# BBB_CNC_V2.net
KiCad netlist of a schematic drawn in EAGLE
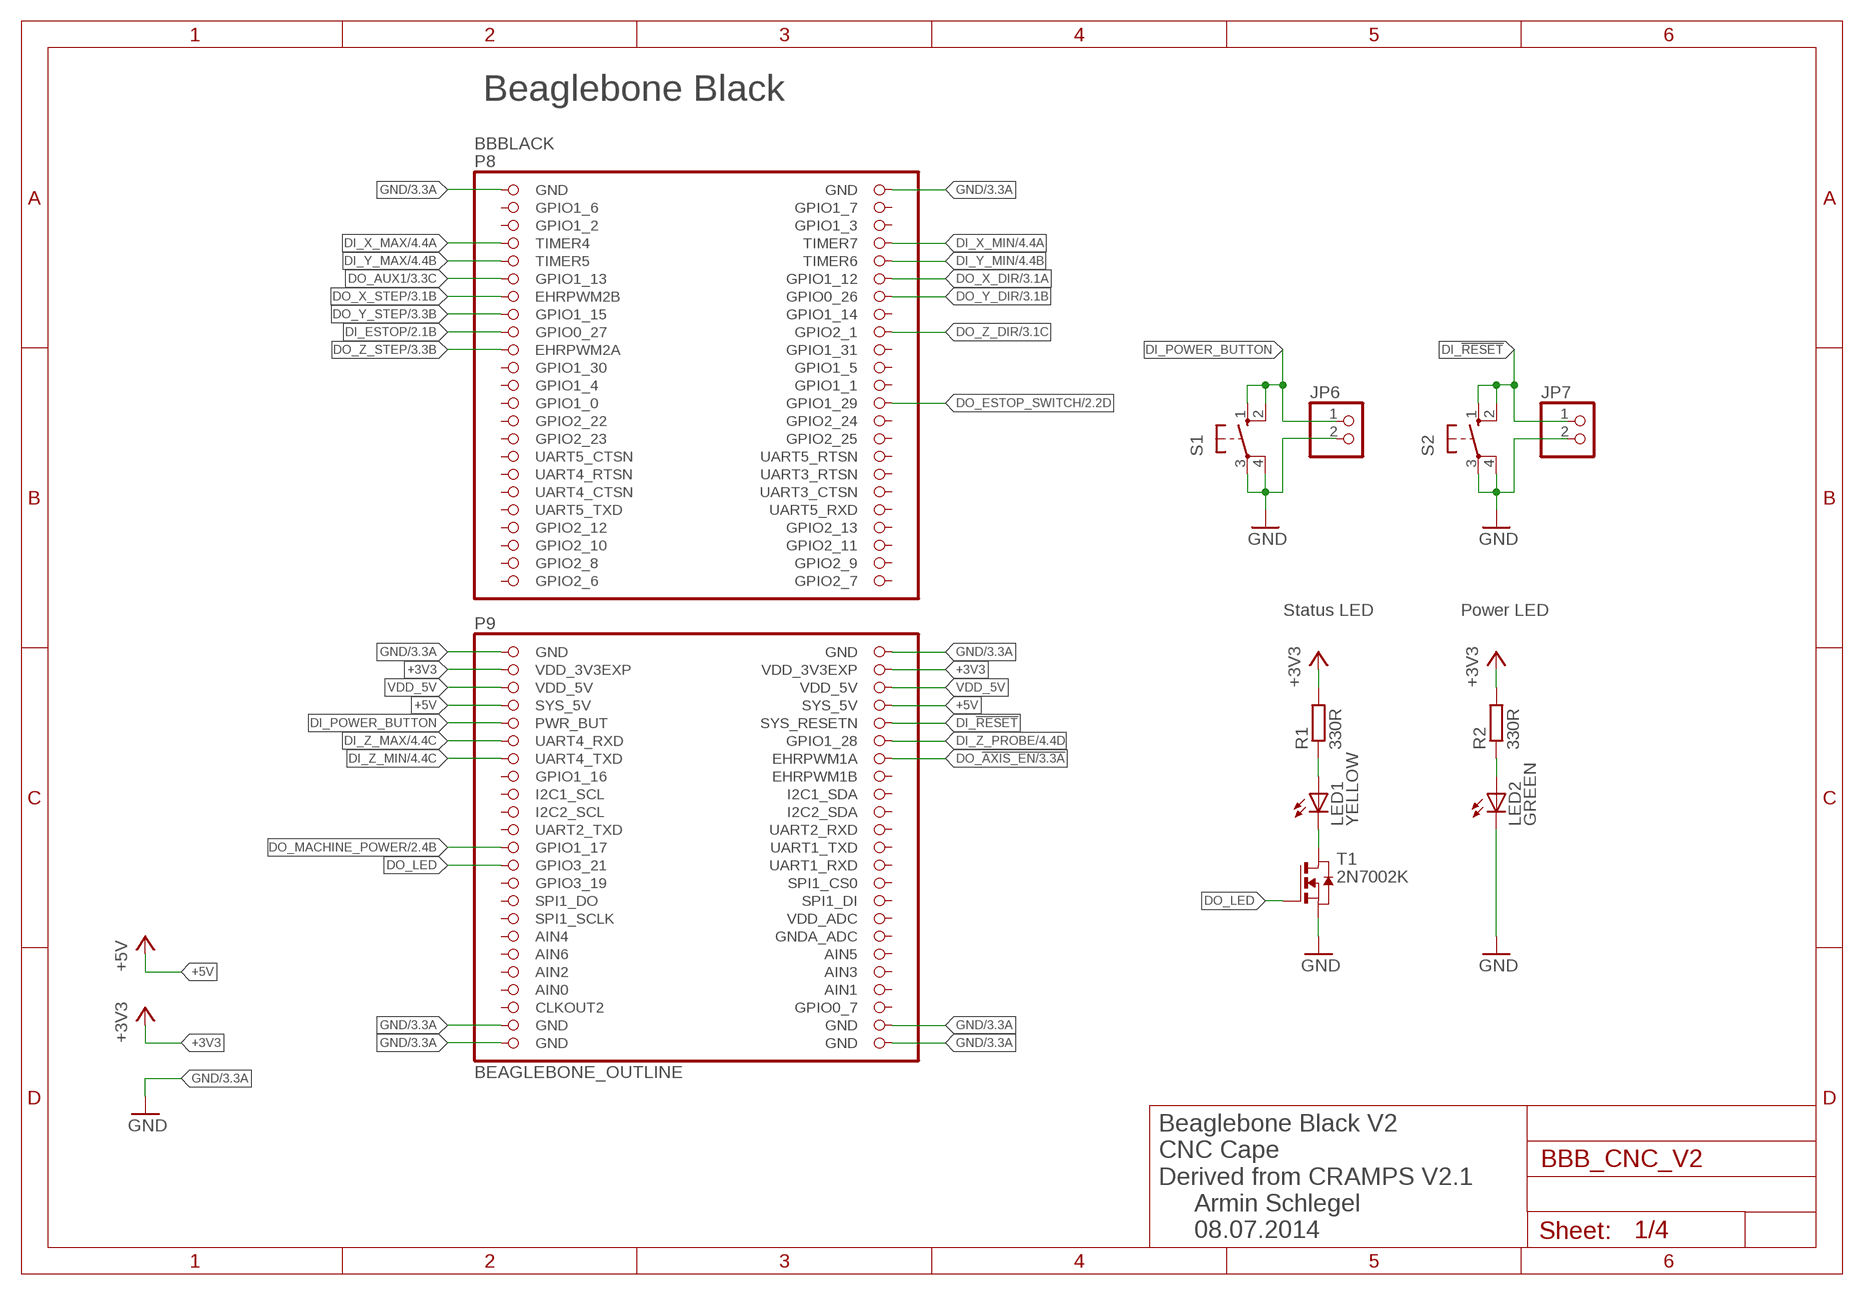
[diagram p0: schematic, sheet 1]
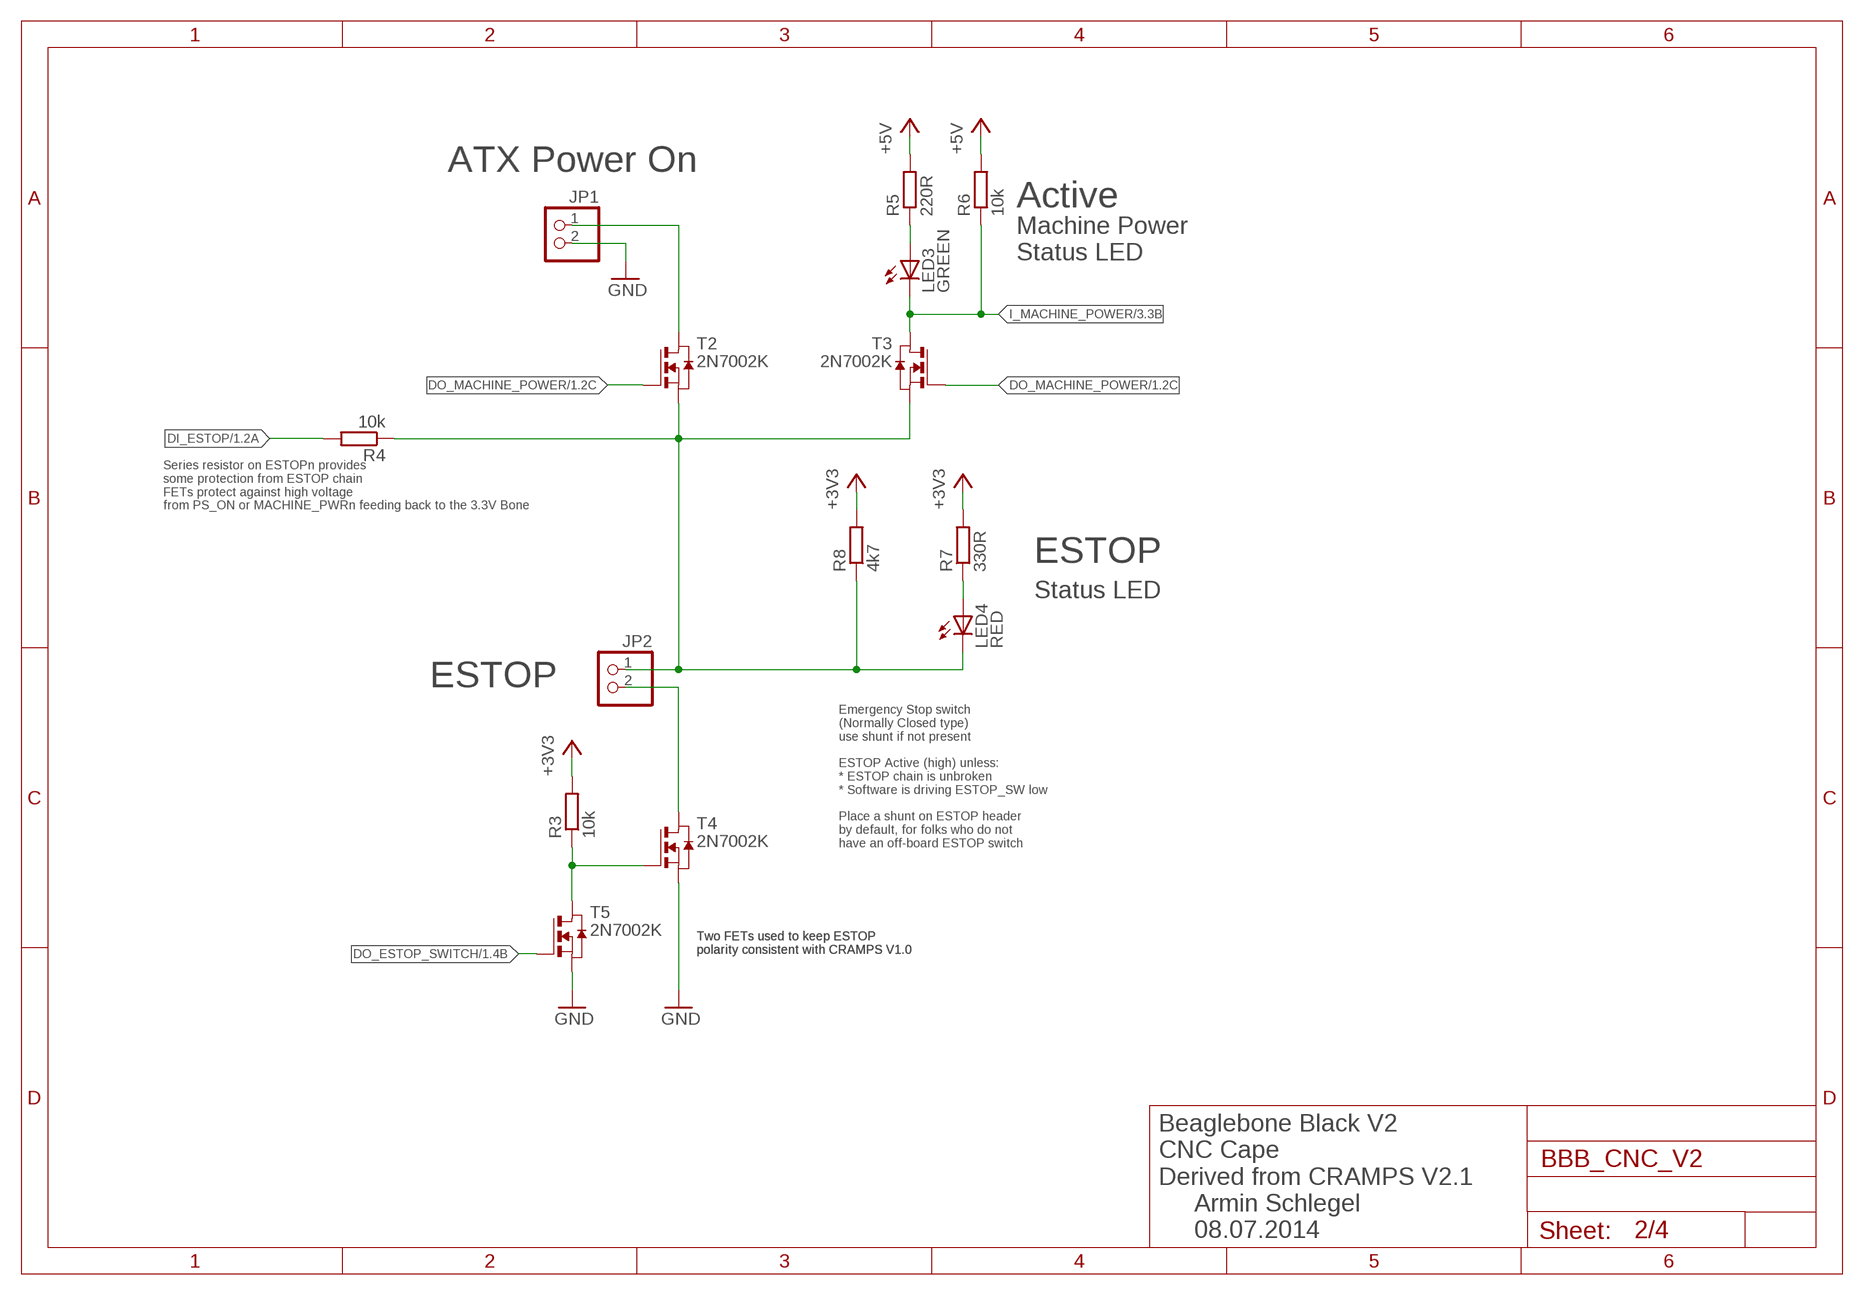
[diagram p1: schematic, sheet 2]
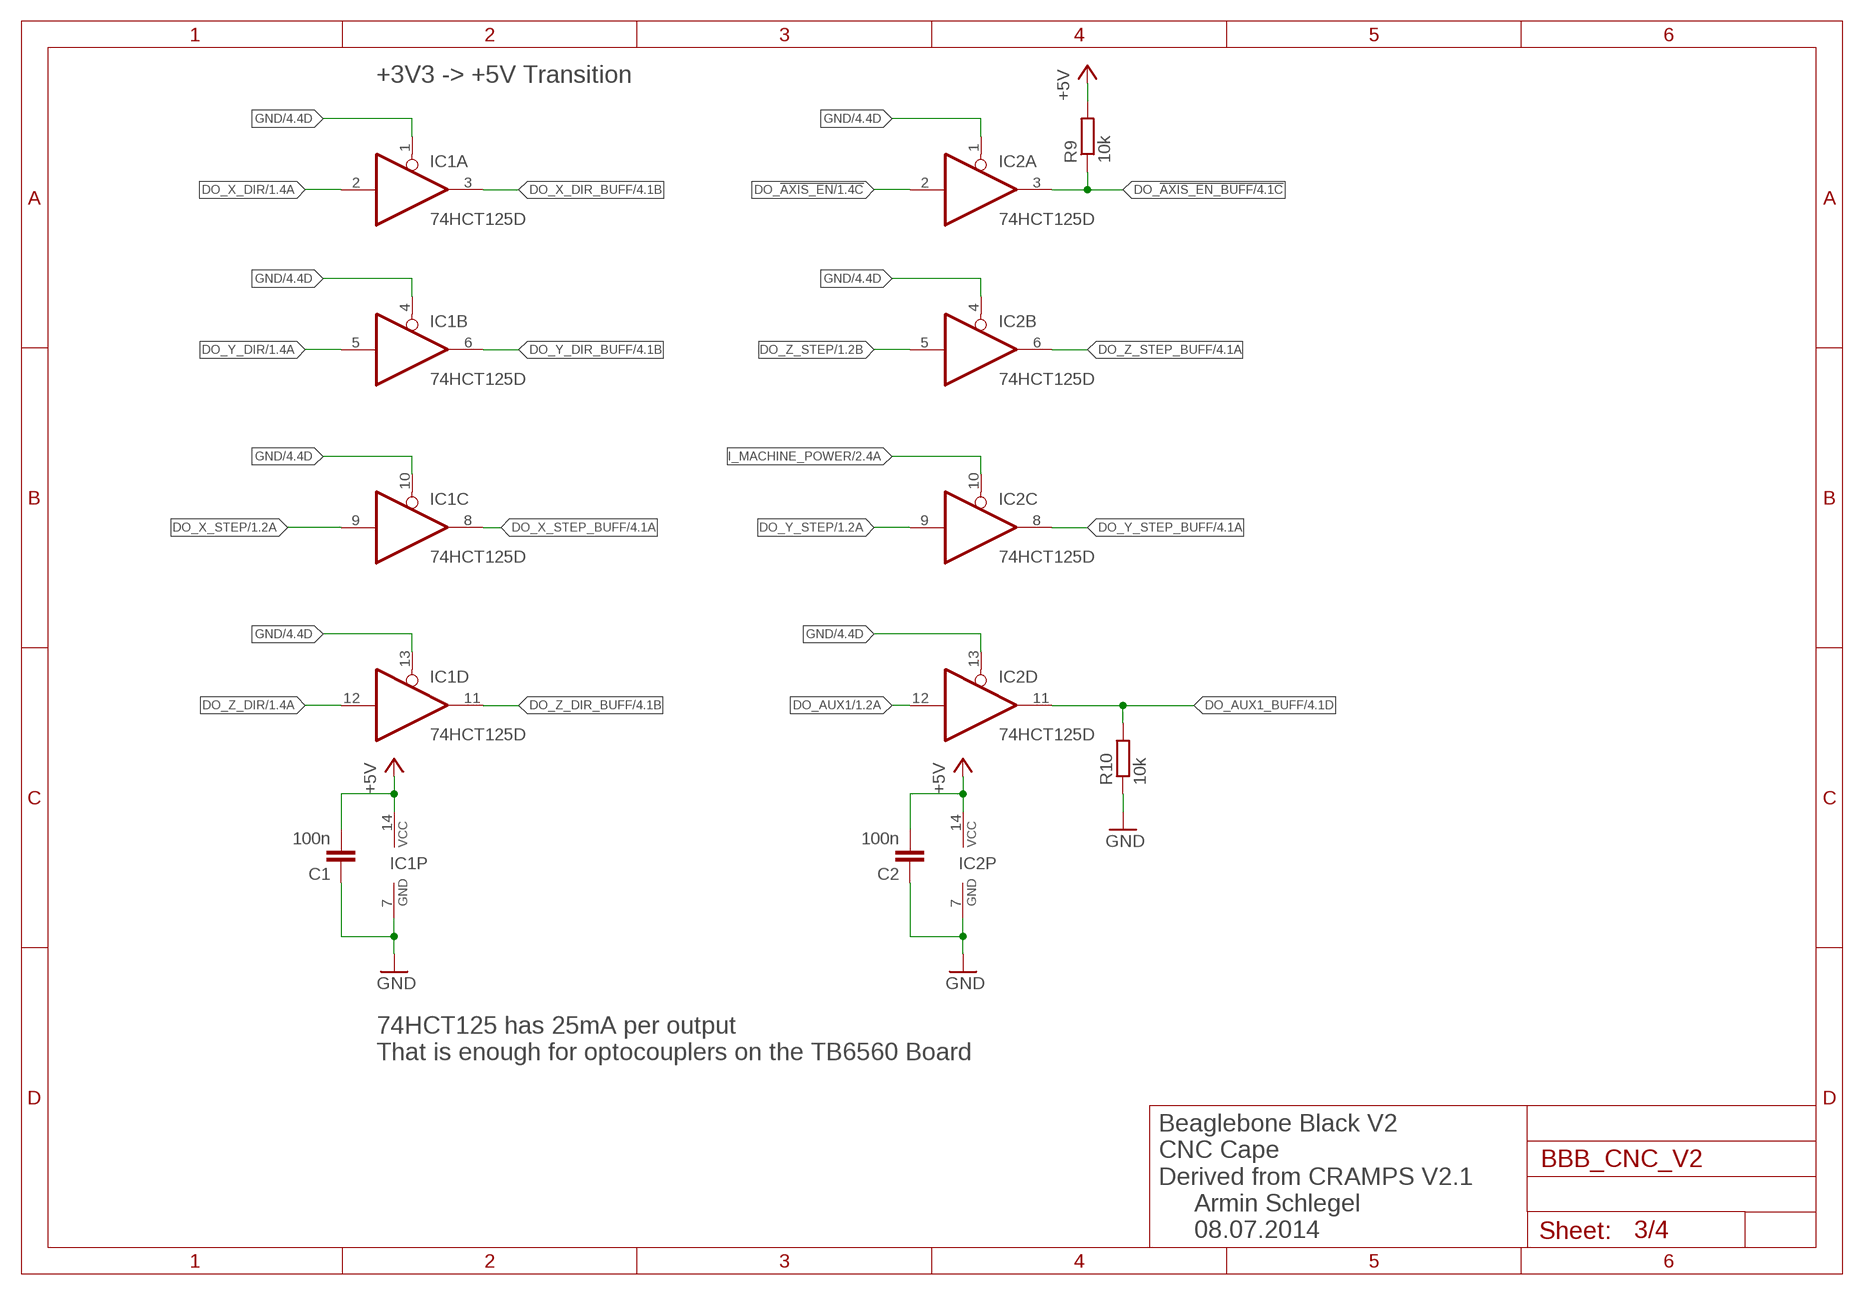
[diagram p2: schematic, sheet 3]
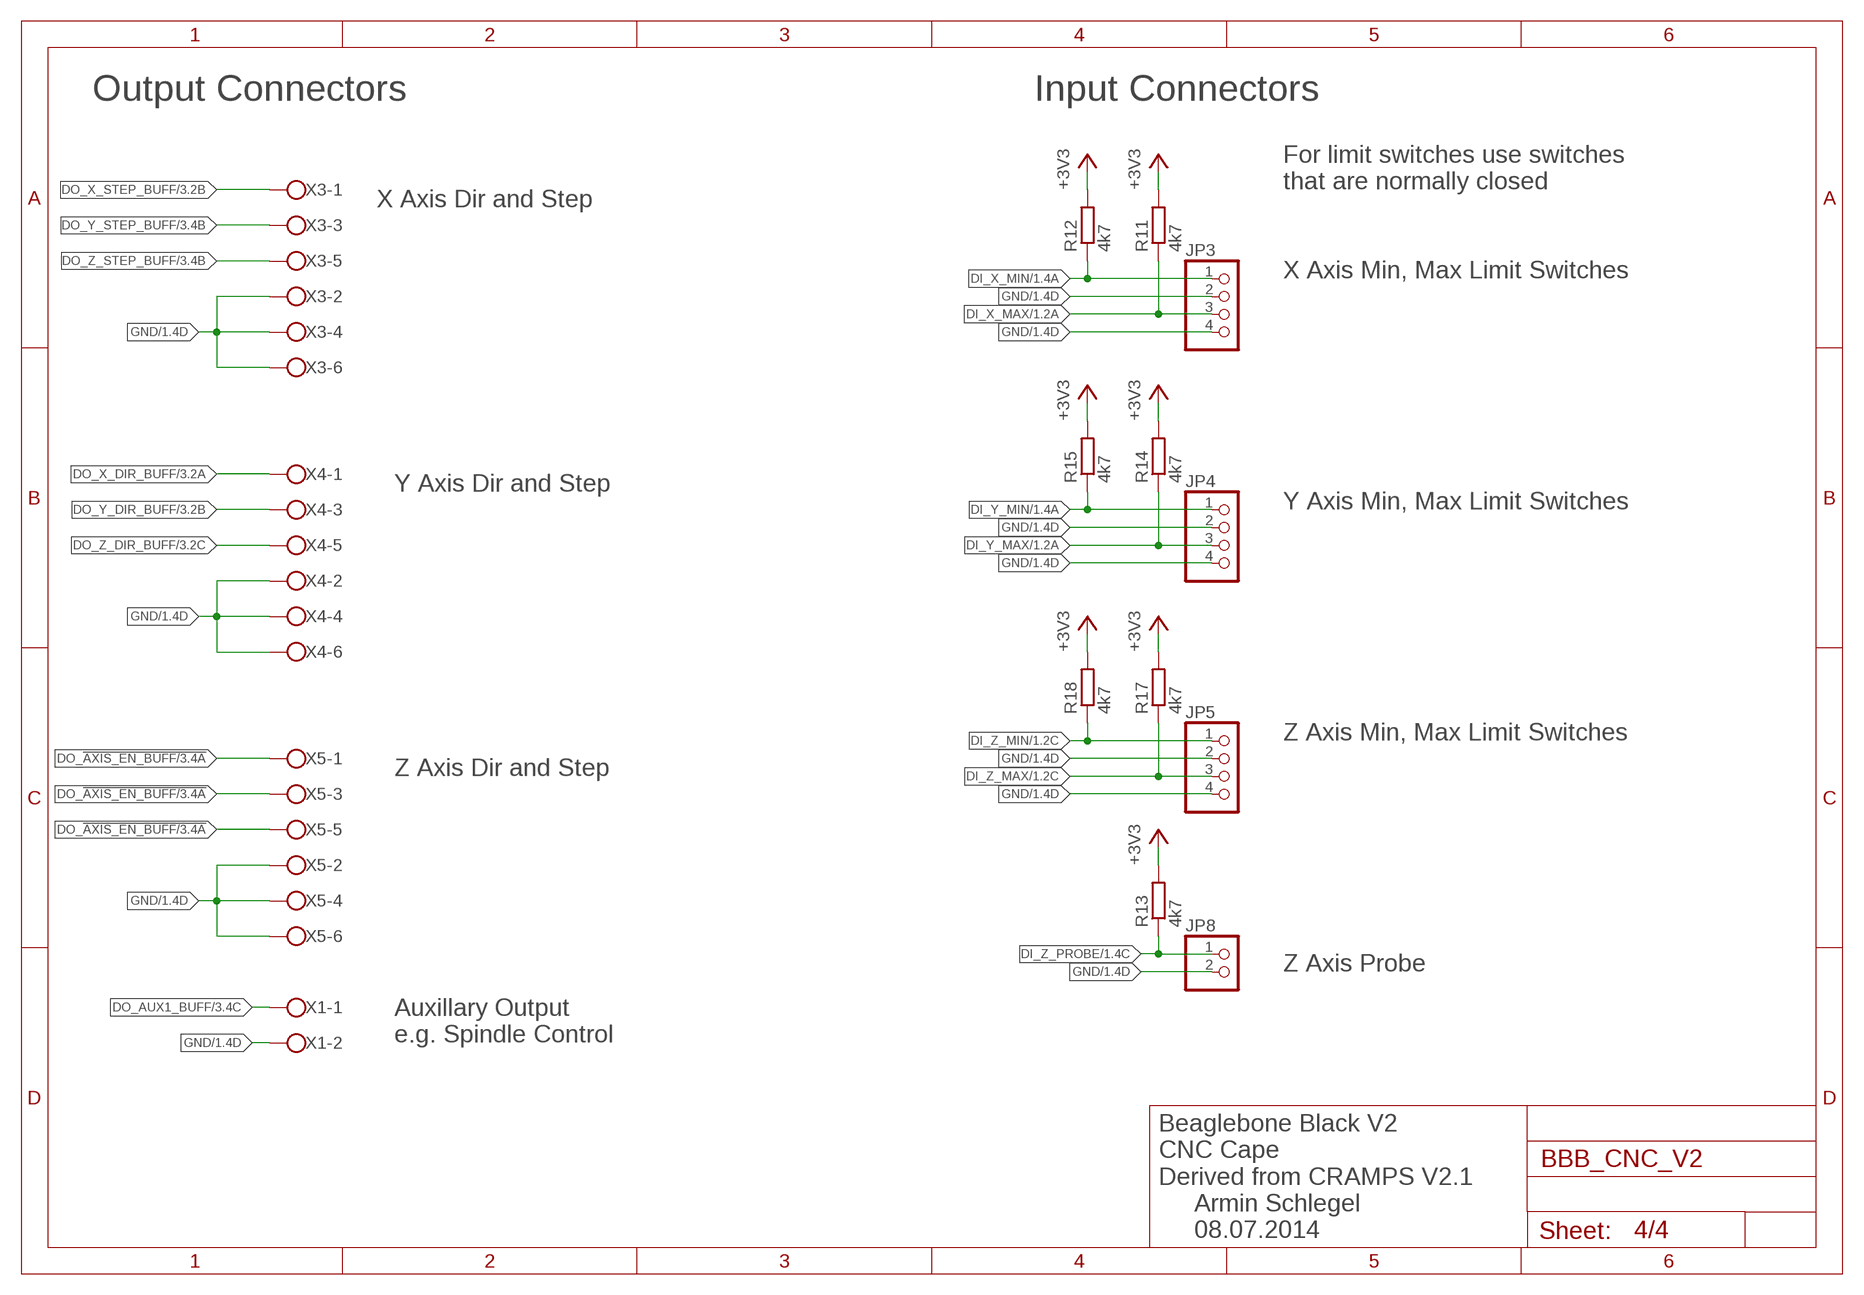
[diagram p3: schematic, sheet 4]

(export (version "E")
  (design (tool "Eeschema 10.0.6"))
  (components
    (comp (ref "BBBLACK")
      (value "BEAGLEBONE_OUTLINE")
      (footprint "eagle-import:BEAGLEBONE_SHIELD")
      (libsource (lib "eagle-import") (part "BEAGLEBONE_OUTLINE"))
    )
    (comp (ref "JP6")
      (value "PINHD-1X2")
      (footprint "eagle-import:1X02")
      (libsource (lib "eagle-import") (part "PINHD-1X2"))
    )
    (comp (ref "JP7")
      (value "PINHD-1X2")
      (footprint "eagle-import:1X02")
      (libsource (lib "eagle-import") (part "PINHD-1X2"))
    )
    (comp (ref "LED1")
      (value "YELLOW")
      (footprint "eagle-import:SML0805")
      (libsource (lib "eagle-import") (part "LEDSML0805"))
    )
    (comp (ref "LED2")
      (value "GREEN")
      (footprint "eagle-import:SML0805")
      (libsource (lib "eagle-import") (part "LEDSML0805"))
    )
    (comp (ref "R1")
      (value "330R")
      (footprint "eagle-import:R0603")
      (libsource (lib "eagle-import") (part "R-EU_R0603"))
    )
    (comp (ref "R2")
      (value "330R")
      (footprint "eagle-import:R0603")
      (libsource (lib "eagle-import") (part "R-EU_R0603"))
    )
    (comp (ref "S1")
      (value "10-XX")
      (footprint "eagle-import:B3F-10XX")
      (fields (field (name "MPN") "B3F-1000"))
      (libsource (lib "eagle-import") (part "10-XX"))
    )
    (comp (ref "S2")
      (value "10-XX")
      (footprint "eagle-import:B3F-10XX")
      (fields (field (name "MPN") "B3F-1000"))
      (libsource (lib "eagle-import") (part "10-XX"))
    )
    (comp (ref "T1")
      (value "2N7002K")
      (footprint "eagle-import:SOT-23")
      (libsource (lib "eagle-import") (part "NMOSSOT23"))
    )
    (comp (ref "JP1")
      (value "PINHD-1X2")
      (footprint "eagle-import:1X02")
      (libsource (lib "eagle-import") (part "PINHD-1X2"))
    )
    (comp (ref "JP2")
      (value "PINHD-1X2")
      (footprint "eagle-import:1X02")
      (libsource (lib "eagle-import") (part "PINHD-1X2"))
    )
    (comp (ref "LED3")
      (value "GREEN")
      (footprint "eagle-import:SML0805")
      (libsource (lib "eagle-import") (part "LEDSML0805"))
    )
    (comp (ref "LED4")
      (value "RED")
      (footprint "eagle-import:SML0805")
      (libsource (lib "eagle-import") (part "LEDSML0805"))
    )
    (comp (ref "R3")
      (value "10k")
      (footprint "eagle-import:R0603")
      (libsource (lib "eagle-import") (part "R-EU_R0603"))
    )
    (comp (ref "R4")
      (value "10k")
      (footprint "eagle-import:R0603")
      (libsource (lib "eagle-import") (part "R-EU_R0603"))
    )
    (comp (ref "R5")
      (value "220R")
      (footprint "eagle-import:R0603")
      (libsource (lib "eagle-import") (part "R-EU_R0603"))
    )
    (comp (ref "R6")
      (value "10k")
      (footprint "eagle-import:R0603")
      (libsource (lib "eagle-import") (part "R-EU_R0603"))
    )
    (comp (ref "R7")
      (value "330R")
      (footprint "eagle-import:R0603")
      (libsource (lib "eagle-import") (part "R-EU_R0603"))
    )
    (comp (ref "R8")
      (value "4k7")
      (footprint "eagle-import:R0603")
      (libsource (lib "eagle-import") (part "R-EU_R0603"))
    )
    (comp (ref "T2")
      (value "2N7002K")
      (footprint "eagle-import:SOT-23")
      (libsource (lib "eagle-import") (part "NMOSSOT23"))
    )
    (comp (ref "T3")
      (value "2N7002K")
      (footprint "eagle-import:SOT-23")
      (libsource (lib "eagle-import") (part "NMOSSOT23"))
    )
    (comp (ref "T4")
      (value "2N7002K")
      (footprint "eagle-import:SOT-23")
      (libsource (lib "eagle-import") (part "NMOSSOT23"))
    )
    (comp (ref "T5")
      (value "2N7002K")
      (footprint "eagle-import:SOT-23")
      (libsource (lib "eagle-import") (part "NMOSSOT23"))
    )
    (comp (ref "C1")
      (value "100n")
      (footprint "eagle-import:C0603K")
      (libsource (lib "eagle-import") (part "C-EUC0603K"))
    )
    (comp (ref "C2")
      (value "100n")
      (footprint "eagle-import:C0603K")
      (libsource (lib "eagle-import") (part "C-EUC0603K"))
    )
    (comp (ref "IC1")
      (value "74HCT125D")
      (footprint "eagle-import:SO14")
      (libsource (lib "eagle-import") (part "74125DHCT"))
    )
    (comp (ref "IC2")
      (value "74HCT125D")
      (footprint "eagle-import:SO14")
      (libsource (lib "eagle-import") (part "74125DHCT"))
    )
    (comp (ref "R9")
      (value "10k")
      (footprint "eagle-import:R0603")
      (libsource (lib "eagle-import") (part "R-EU_R0603"))
    )
    (comp (ref "R10")
      (value "10k")
      (footprint "eagle-import:R0603")
      (libsource (lib "eagle-import") (part "R-EU_R0603"))
    )
    (comp (ref "JP3")
      (value "PINHD-1X4")
      (footprint "eagle-import:1X04")
      (libsource (lib "eagle-import") (part "PINHD-1X4"))
    )
    (comp (ref "JP4")
      (value "PINHD-1X4")
      (footprint "eagle-import:1X04")
      (libsource (lib "eagle-import") (part "PINHD-1X4"))
    )
    (comp (ref "JP5")
      (value "PINHD-1X4")
      (footprint "eagle-import:1X04")
      (libsource (lib "eagle-import") (part "PINHD-1X4"))
    )
    (comp (ref "JP8")
      (value "PINHD-1X2")
      (footprint "eagle-import:1X02")
      (libsource (lib "eagle-import") (part "PINHD-1X2"))
    )
    (comp (ref "R11")
      (value "4k7")
      (footprint "eagle-import:R0603")
      (libsource (lib "eagle-import") (part "R-EU_R0603"))
    )
    (comp (ref "R12")
      (value "4k7")
      (footprint "eagle-import:R0603")
      (libsource (lib "eagle-import") (part "R-EU_R0603"))
    )
    (comp (ref "R13")
      (value "4k7")
      (footprint "eagle-import:R0603")
      (libsource (lib "eagle-import") (part "R-EU_R0603"))
    )
    (comp (ref "R14")
      (value "4k7")
      (footprint "eagle-import:R0603")
      (libsource (lib "eagle-import") (part "R-EU_R0603"))
    )
    (comp (ref "R15")
      (value "4k7")
      (footprint "eagle-import:R0603")
      (libsource (lib "eagle-import") (part "R-EU_R0603"))
    )
    (comp (ref "R17")
      (value "4k7")
      (footprint "eagle-import:R0603")
      (libsource (lib "eagle-import") (part "R-EU_R0603"))
    )
    (comp (ref "R18")
      (value "4k7")
      (footprint "eagle-import:R0603")
      (libsource (lib "eagle-import") (part "R-EU_R0603"))
    )
    (comp (ref "X1")
      (value "W237-102")
      (footprint "eagle-import:W237-102")
      (fields (field (name "MPN") "237-102"))
      (libsource (lib "eagle-import") (part "W237-102"))
    )
    (comp (ref "X3")
      (value "W237-136")
      (footprint "eagle-import:W237-136")
      (fields (field (name "MPN") "237-136"))
      (libsource (lib "eagle-import") (part "W237-136"))
    )
    (comp (ref "X4")
      (value "W237-136")
      (footprint "eagle-import:W237-136")
      (fields (field (name "MPN") "237-136"))
      (libsource (lib "eagle-import") (part "W237-136"))
    )
    (comp (ref "X5")
      (value "W237-136")
      (footprint "eagle-import:W237-136")
      (fields (field (name "MPN") "237-136"))
      (libsource (lib "eagle-import") (part "W237-136"))
    )
  )
  (nets
    (net (code "1") (name "+3V3") (class "Default")
      (node (ref "BBBLACK") (pin "49") (pinfunction "VDD_3V3EXP_49") (pintype "power_in"))
      (node (ref "BBBLACK") (pin "50") (pinfunction "VDD_3V3EXP_50") (pintype "power_in"))
      (node (ref "R1") (pin "2") (pinfunction "2_2") (pintype "passive"))
      (node (ref "R11") (pin "2") (pinfunction "2_2") (pintype "passive"))
      (node (ref "R12") (pin "2") (pinfunction "2_2") (pintype "passive"))
      (node (ref "R13") (pin "2") (pinfunction "2_2") (pintype "passive"))
      (node (ref "R14") (pin "2") (pinfunction "2_2") (pintype "passive"))
      (node (ref "R15") (pin "2") (pinfunction "2_2") (pintype "passive"))
      (node (ref "R17") (pin "2") (pinfunction "2_2") (pintype "passive"))
      (node (ref "R18") (pin "2") (pinfunction "2_2") (pintype "passive"))
      (node (ref "R2") (pin "2") (pinfunction "2_2") (pintype "passive"))
      (node (ref "R3") (pin "2") (pinfunction "2_2") (pintype "passive"))
      (node (ref "R7") (pin "2") (pinfunction "2_2") (pintype "passive"))
      (node (ref "R8") (pin "2") (pinfunction "2_2") (pintype "passive"))
    )
    (net (code "2") (name "+5V") (class "Default")
      (node (ref "BBBLACK") (pin "53") (pinfunction "SYS_5V_53") (pintype "power_in"))
      (node (ref "BBBLACK") (pin "54") (pinfunction "SYS_5V_54") (pintype "passive"))
      (node (ref "C1") (pin "2") (pinfunction "2_2") (pintype "passive"))
      (node (ref "C2") (pin "2") (pinfunction "2_2") (pintype "passive"))
      (node (ref "IC1") (pin "14") (pinfunction "VCC_14") (pintype "power_in"))
      (node (ref "IC2") (pin "14") (pinfunction "VCC_14") (pintype "power_in"))
      (node (ref "R5") (pin "2") (pinfunction "2_2") (pintype "passive"))
      (node (ref "R6") (pin "2") (pinfunction "2_2") (pintype "passive"))
      (node (ref "R9") (pin "2") (pinfunction "2_2") (pintype "passive"))
    )
    (net (code "3") (name "AIN0") (class "Default")
      (node (ref "BBBLACK") (pin "85") (pinfunction "AIN0_85") (pintype "power_in"))
    )
    (net (code "4") (name "DI_ESTOP") (class "Default")
      (node (ref "BBBLACK") (pin "17") (pinfunction "GPIO0_27_17") (pintype "passive"))
      (node (ref "R4") (pin "2") (pinfunction "2_2") (pintype "passive"))
    )
    (net (code "5") (name "DI_POWER_BUTTON") (class "Default")
      (node (ref "BBBLACK") (pin "55") (pinfunction "PWR_BUT_55") (pintype "passive"))
      (node (ref "JP6") (pin "1") (pinfunction "1_1") (pintype "passive"))
      (node (ref "S1") (pin "1") (pinfunction "S_1") (pintype "passive"))
      (node (ref "S1") (pin "2") (pinfunction "S1_2") (pintype "passive"))
    )
    (net (code "6") (name "DI_X_MAX") (class "Default")
      (node (ref "BBBLACK") (pin "7") (pinfunction "TIMER4_7") (pintype "passive"))
      (node (ref "JP3") (pin "3") (pinfunction "3_3") (pintype "passive"))
      (node (ref "R11") (pin "1") (pinfunction "1_1") (pintype "passive"))
    )
    (net (code "7") (name "DI_X_MIN") (class "Default")
      (node (ref "BBBLACK") (pin "8") (pinfunction "TIMER7_8") (pintype "passive"))
      (node (ref "JP3") (pin "1") (pinfunction "1_1") (pintype "passive"))
      (node (ref "R12") (pin "1") (pinfunction "1_1") (pintype "passive"))
    )
    (net (code "8") (name "DI_Y_MAX") (class "Default")
      (node (ref "BBBLACK") (pin "9") (pinfunction "TIMER5_9") (pintype "passive"))
      (node (ref "JP4") (pin "3") (pinfunction "3_3") (pintype "passive"))
      (node (ref "R14") (pin "1") (pinfunction "1_1") (pintype "passive"))
    )
    (net (code "9") (name "DI_Y_MIN") (class "Default")
      (node (ref "BBBLACK") (pin "10") (pinfunction "TIMER6_10") (pintype "passive"))
      (node (ref "JP4") (pin "1") (pinfunction "1_1") (pintype "passive"))
      (node (ref "R15") (pin "1") (pinfunction "1_1") (pintype "passive"))
    )
    (net (code "10") (name "DI_Z_MAX") (class "Default")
      (node (ref "BBBLACK") (pin "57") (pinfunction "UART4_RXD_57") (pintype "passive"))
      (node (ref "JP5") (pin "3") (pinfunction "3_3") (pintype "passive"))
      (node (ref "R17") (pin "1") (pinfunction "1_1") (pintype "passive"))
    )
    (net (code "11") (name "DI_Z_MIN") (class "Default")
      (node (ref "BBBLACK") (pin "59") (pinfunction "UART4_TXD_59") (pintype "passive"))
      (node (ref "JP5") (pin "1") (pinfunction "1_1") (pintype "passive"))
      (node (ref "R18") (pin "1") (pinfunction "1_1") (pintype "passive"))
    )
    (net (code "12") (name "DI_Z_PROBE") (class "Default")
      (node (ref "BBBLACK") (pin "58") (pinfunction "GPIO1_28_58") (pintype "passive"))
      (node (ref "JP8") (pin "1") (pinfunction "1_1") (pintype "passive"))
      (node (ref "R13") (pin "1") (pinfunction "1_1") (pintype "passive"))
    )
    (net (code "13") (name "DI_~{RESET}") (class "Default")
      (node (ref "BBBLACK") (pin "56") (pinfunction "SYS_RESETN_56") (pintype "passive"))
      (node (ref "JP7") (pin "1") (pinfunction "1_1") (pintype "passive"))
      (node (ref "S2") (pin "1") (pinfunction "S_1") (pintype "passive"))
      (node (ref "S2") (pin "2") (pinfunction "S1_2") (pintype "passive"))
    )
    (net (code "14") (name "DO_AUX1") (class "Default")
      (node (ref "BBBLACK") (pin "11") (pinfunction "GPIO1_13_11") (pintype "passive"))
      (node (ref "IC2") (pin "12") (pinfunction "I_12") (pintype "input"))
    )
    (net (code "15") (name "DO_AUX1_BUFF") (class "Default")
      (node (ref "IC2") (pin "11") (pinfunction "O_11") (pintype "tri_state"))
      (node (ref "R10") (pin "2") (pinfunction "2_2") (pintype "passive"))
      (node (ref "X1") (pin "1") (pinfunction "KL_1") (pintype "passive"))
    )
    (net (code "16") (name "DO_ESTOP_SWITCH") (class "Default")
      (node (ref "BBBLACK") (pin "26") (pinfunction "GPIO1_29_26") (pintype "passive"))
      (node (ref "T5") (pin "3") (pinfunction "G_3") (pintype "passive"))
    )
    (net (code "17") (name "DO_LED") (class "Default")
      (node (ref "BBBLACK") (pin "71") (pinfunction "GPIO3_21_71") (pintype "passive"))
      (node (ref "T1") (pin "3") (pinfunction "G_3") (pintype "passive"))
    )
    (net (code "18") (name "DO_MACHINE_POWER") (class "Default")
      (node (ref "BBBLACK") (pin "69") (pinfunction "GPIO1_17_69") (pintype "passive"))
      (node (ref "T2") (pin "3") (pinfunction "G_3") (pintype "passive"))
      (node (ref "T3") (pin "3") (pinfunction "G_3") (pintype "passive"))
    )
    (net (code "19") (name "DO_X_DIR") (class "Default")
      (node (ref "BBBLACK") (pin "12") (pinfunction "GPIO1_12_12") (pintype "passive"))
      (node (ref "IC1") (pin "2") (pinfunction "I_2") (pintype "input"))
    )
    (net (code "20") (name "DO_X_DIR_BUFF") (class "Default")
      (node (ref "IC1") (pin "3") (pinfunction "O_3") (pintype "tri_state"))
      (node (ref "X4") (pin "1") (pinfunction "KL_1") (pintype "passive"))
    )
    (net (code "21") (name "DO_X_STEP") (class "Default")
      (node (ref "BBBLACK") (pin "13") (pinfunction "EHRPWM2B_13") (pintype "passive"))
      (node (ref "IC1") (pin "9") (pinfunction "I_9") (pintype "input"))
    )
    (net (code "22") (name "DO_X_STEP_BUFF") (class "Default")
      (node (ref "IC1") (pin "8") (pinfunction "O_8") (pintype "tri_state"))
      (node (ref "X3") (pin "1") (pinfunction "KL_1") (pintype "passive"))
    )
    (net (code "23") (name "DO_Y_DIR") (class "Default")
      (node (ref "BBBLACK") (pin "14") (pinfunction "GPIO0_26_14") (pintype "passive"))
      (node (ref "IC1") (pin "5") (pinfunction "I_5") (pintype "input"))
    )
    (net (code "24") (name "DO_Y_DIR_BUFF") (class "Default")
      (node (ref "IC1") (pin "6") (pinfunction "O_6") (pintype "tri_state"))
      (node (ref "X4") (pin "3") (pinfunction "KL_3") (pintype "passive"))
    )
    (net (code "25") (name "DO_Y_STEP") (class "Default")
      (node (ref "BBBLACK") (pin "15") (pinfunction "GPIO1_15_15") (pintype "passive"))
      (node (ref "IC2") (pin "9") (pinfunction "I_9") (pintype "input"))
    )
    (net (code "26") (name "DO_Y_STEP_BUFF") (class "Default")
      (node (ref "IC2") (pin "8") (pinfunction "O_8") (pintype "tri_state"))
      (node (ref "X3") (pin "3") (pinfunction "KL_3") (pintype "passive"))
    )
    (net (code "27") (name "DO_Z_DIR") (class "Default")
      (node (ref "BBBLACK") (pin "18") (pinfunction "GPIO2_1_18") (pintype "passive"))
      (node (ref "IC1") (pin "12") (pinfunction "I_12") (pintype "input"))
    )
    (net (code "28") (name "DO_Z_DIR_BUFF") (class "Default")
      (node (ref "IC1") (pin "11") (pinfunction "O_11") (pintype "tri_state"))
      (node (ref "X4") (pin "5") (pinfunction "KL_5") (pintype "passive"))
    )
    (net (code "29") (name "DO_Z_STEP") (class "Default")
      (node (ref "BBBLACK") (pin "19") (pinfunction "EHRPWM2A_19") (pintype "passive"))
      (node (ref "IC2") (pin "5") (pinfunction "I_5") (pintype "input"))
    )
    (net (code "30") (name "DO_Z_STEP_BUFF") (class "Default")
      (node (ref "IC2") (pin "6") (pinfunction "O_6") (pintype "tri_state"))
      (node (ref "X3") (pin "5") (pinfunction "KL_5") (pintype "passive"))
    )
    (net (code "31") (name "DO_~{AXIS_EN_BUFF}") (class "Default")
      (node (ref "IC2") (pin "3") (pinfunction "O_3") (pintype "tri_state"))
      (node (ref "R9") (pin "1") (pinfunction "1_1") (pintype "passive"))
      (node (ref "X5") (pin "1") (pinfunction "KL_1") (pintype "passive"))
      (node (ref "X5") (pin "3") (pinfunction "KL_3") (pintype "passive"))
      (node (ref "X5") (pin "5") (pinfunction "KL_5") (pintype "passive"))
    )
    (net (code "32") (name "DO_~{AXIS_EN}") (class "Default")
      (node (ref "BBBLACK") (pin "60") (pinfunction "EHRPWM1A_60") (pintype "passive"))
      (node (ref "IC2") (pin "2") (pinfunction "I_2") (pintype "input"))
    )
    (net (code "33") (name "GND") (class "Default")
      (node (ref "BBBLACK") (pin "1") (pinfunction "GND_1") (pintype "power_in"))
      (node (ref "BBBLACK") (pin "2") (pinfunction "GND_2") (pintype "power_in"))
      (node (ref "BBBLACK") (pin "47") (pinfunction "GND_47") (pintype "power_in"))
      (node (ref "BBBLACK") (pin "48") (pinfunction "GND_48") (pintype "power_in"))
      (node (ref "BBBLACK") (pin "89") (pinfunction "GND_89") (pintype "power_in"))
      (node (ref "BBBLACK") (pin "90") (pinfunction "GND_90") (pintype "power_in"))
      (node (ref "BBBLACK") (pin "91") (pinfunction "GND_91") (pintype "power_in"))
      (node (ref "BBBLACK") (pin "92") (pinfunction "GND_92") (pintype "power_in"))
      (node (ref "C1") (pin "1") (pinfunction "1_1") (pintype "passive"))
      (node (ref "C2") (pin "1") (pinfunction "1_1") (pintype "passive"))
      (node (ref "IC1") (pin "1") (pinfunction "OE_1") (pintype "input"))
      (node (ref "IC1") (pin "10") (pinfunction "OE_10") (pintype "input"))
      (node (ref "IC1") (pin "13") (pinfunction "OE_13") (pintype "input"))
      (node (ref "IC1") (pin "4") (pinfunction "OE_4") (pintype "input"))
      (node (ref "IC1") (pin "7") (pinfunction "GND_7") (pintype "power_in"))
      (node (ref "IC2") (pin "1") (pinfunction "OE_1") (pintype "input"))
      (node (ref "IC2") (pin "13") (pinfunction "OE_13") (pintype "input"))
      (node (ref "IC2") (pin "4") (pinfunction "OE_4") (pintype "input"))
      (node (ref "IC2") (pin "7") (pinfunction "GND_7") (pintype "power_in"))
      (node (ref "JP1") (pin "2") (pinfunction "2_2") (pintype "passive"))
      (node (ref "JP3") (pin "2") (pinfunction "2_2") (pintype "passive"))
      (node (ref "JP3") (pin "4") (pinfunction "4_4") (pintype "passive"))
      (node (ref "JP4") (pin "2") (pinfunction "2_2") (pintype "passive"))
      (node (ref "JP4") (pin "4") (pinfunction "4_4") (pintype "passive"))
      (node (ref "JP5") (pin "2") (pinfunction "2_2") (pintype "passive"))
      (node (ref "JP5") (pin "4") (pinfunction "4_4") (pintype "passive"))
      (node (ref "JP6") (pin "2") (pinfunction "2_2") (pintype "passive"))
      (node (ref "JP7") (pin "2") (pinfunction "2_2") (pintype "passive"))
      (node (ref "JP8") (pin "2") (pinfunction "2_2") (pintype "passive"))
      (node (ref "LED2") (pin "C") (pinfunction "C_C") (pintype "passive"))
      (node (ref "R10") (pin "1") (pinfunction "1_1") (pintype "passive"))
      (node (ref "S1") (pin "3") (pinfunction "P_3") (pintype "passive"))
      (node (ref "S1") (pin "4") (pinfunction "P1_4") (pintype "passive"))
      (node (ref "S2") (pin "3") (pinfunction "P_3") (pintype "passive"))
      (node (ref "S2") (pin "4") (pinfunction "P1_4") (pintype "passive"))
      (node (ref "T1") (pin "2") (pinfunction "S_2") (pintype "passive"))
      (node (ref "T4") (pin "2") (pinfunction "S_2") (pintype "passive"))
      (node (ref "T5") (pin "2") (pinfunction "S_2") (pintype "passive"))
      (node (ref "X1") (pin "2") (pinfunction "KL_2") (pintype "passive"))
      (node (ref "X3") (pin "2") (pinfunction "KL_2") (pintype "passive"))
      (node (ref "X3") (pin "4") (pinfunction "KL_4") (pintype "passive"))
      (node (ref "X3") (pin "6") (pinfunction "KL_6") (pintype "passive"))
      (node (ref "X4") (pin "2") (pinfunction "KL_2") (pintype "passive"))
      (node (ref "X4") (pin "4") (pinfunction "KL_4") (pintype "passive"))
      (node (ref "X4") (pin "6") (pinfunction "KL_6") (pintype "passive"))
      (node (ref "X5") (pin "2") (pinfunction "KL_2") (pintype "passive"))
      (node (ref "X5") (pin "4") (pinfunction "KL_4") (pintype "passive"))
      (node (ref "X5") (pin "6") (pinfunction "KL_6") (pintype "passive"))
    )
    (net (code "34") (name "I_MACHINE_POWER") (class "Default")
      (node (ref "IC2") (pin "10") (pinfunction "OE_10") (pintype "input"))
      (node (ref "LED3") (pin "C") (pinfunction "C_C") (pintype "passive"))
      (node (ref "R6") (pin "1") (pinfunction "1_1") (pintype "passive"))
      (node (ref "T3") (pin "1") (pinfunction "D_1") (pintype "passive"))
    )
    (net (code "35") (name "Net-(LED1-PadA)") (class "Default")
      (node (ref "LED1") (pin "A") (pinfunction "A_A") (pintype "passive"))
      (node (ref "R1") (pin "1") (pinfunction "1_1") (pintype "passive"))
    )
    (net (code "36") (name "Net-(LED2-PadA)") (class "Default")
      (node (ref "LED2") (pin "A") (pinfunction "A_A") (pintype "passive"))
      (node (ref "R2") (pin "1") (pinfunction "1_1") (pintype "passive"))
    )
    (net (code "37") (name "Net-(LED3-PadA)") (class "Default")
      (node (ref "LED3") (pin "A") (pinfunction "A_A") (pintype "passive"))
      (node (ref "R5") (pin "1") (pinfunction "1_1") (pintype "passive"))
    )
    (net (code "38") (name "Net-(LED4-PadA)") (class "Default")
      (node (ref "LED4") (pin "A") (pinfunction "A_A") (pintype "passive"))
      (node (ref "R7") (pin "1") (pinfunction "1_1") (pintype "passive"))
    )
    (net (code "39") (name "Net-(T1-D)") (class "Default")
      (node (ref "LED1") (pin "C") (pinfunction "C_C") (pintype "passive"))
      (node (ref "T1") (pin "1") (pinfunction "D_1") (pintype "passive"))
    )
    (net (code "40") (name "Net-(T2-D)") (class "Default")
      (node (ref "JP1") (pin "1") (pinfunction "1_1") (pintype "passive"))
      (node (ref "T2") (pin "1") (pinfunction "D_1") (pintype "passive"))
    )
    (net (code "41") (name "Net-(T2-S)") (class "Default")
      (node (ref "JP2") (pin "1") (pinfunction "1_1") (pintype "passive"))
      (node (ref "LED4") (pin "C") (pinfunction "C_C") (pintype "passive"))
      (node (ref "R4") (pin "1") (pinfunction "1_1") (pintype "passive"))
      (node (ref "R8") (pin "1") (pinfunction "1_1") (pintype "passive"))
      (node (ref "T2") (pin "2") (pinfunction "S_2") (pintype "passive"))
      (node (ref "T3") (pin "2") (pinfunction "S_2") (pintype "passive"))
    )
    (net (code "42") (name "Net-(T4-D)") (class "Default")
      (node (ref "JP2") (pin "2") (pinfunction "2_2") (pintype "passive"))
      (node (ref "T4") (pin "1") (pinfunction "D_1") (pintype "passive"))
    )
    (net (code "43") (name "Net-(T4-G)") (class "Default")
      (node (ref "R3") (pin "1") (pinfunction "1_1") (pintype "passive"))
      (node (ref "T4") (pin "3") (pinfunction "G_3") (pintype "passive"))
      (node (ref "T5") (pin "1") (pinfunction "D_1") (pintype "passive"))
    )
    (net (code "44") (name "VDD_5V") (class "Default")
      (node (ref "BBBLACK") (pin "51") (pinfunction "VDD_5V_51") (pintype "power_in"))
      (node (ref "BBBLACK") (pin "52") (pinfunction "VDD_5V_52") (pintype "power_in"))
    )
    (net (code "45") (name "unconnected-(BBBLACK-AIN1-Pad86)") (class "Default")
      (node (ref "BBBLACK") (pin "86") (pinfunction "AIN1_86") (pintype "passive"))
    )
    (net (code "46") (name "unconnected-(BBBLACK-AIN2-Pad83)") (class "Default")
      (node (ref "BBBLACK") (pin "83") (pinfunction "AIN2_83") (pintype "passive"))
    )
    (net (code "47") (name "unconnected-(BBBLACK-AIN3-Pad84)") (class "Default")
      (node (ref "BBBLACK") (pin "84") (pinfunction "AIN3_84") (pintype "passive"))
    )
    (net (code "48") (name "unconnected-(BBBLACK-AIN4-Pad79)") (class "Default")
      (node (ref "BBBLACK") (pin "79") (pinfunction "AIN4_79") (pintype "passive"))
    )
    (net (code "49") (name "unconnected-(BBBLACK-AIN5-Pad82)") (class "Default")
      (node (ref "BBBLACK") (pin "82") (pinfunction "AIN5_82") (pintype "passive"))
    )
    (net (code "50") (name "unconnected-(BBBLACK-AIN6-Pad81)") (class "Default")
      (node (ref "BBBLACK") (pin "81") (pinfunction "AIN6_81") (pintype "passive"))
    )
    (net (code "51") (name "unconnected-(BBBLACK-CLKOUT2-Pad87)") (class "Default")
      (node (ref "BBBLACK") (pin "87") (pinfunction "CLKOUT2_87") (pintype "input"))
    )
    (net (code "52") (name "unconnected-(BBBLACK-EHRPWM1B-Pad62)") (class "Default")
      (node (ref "BBBLACK") (pin "62") (pinfunction "EHRPWM1B_62") (pintype "passive"))
    )
    (net (code "53") (name "unconnected-(BBBLACK-GNDA_ADC-Pad80)") (class "Default")
      (node (ref "BBBLACK") (pin "80") (pinfunction "GNDA_ADC_80") (pintype "passive"))
    )
    (net (code "54") (name "unconnected-(BBBLACK-GPIO0_7-Pad88)") (class "Default")
      (node (ref "BBBLACK") (pin "88") (pinfunction "GPIO0_7_88") (pintype "passive"))
    )
    (net (code "55") (name "unconnected-(BBBLACK-GPIO1_0-Pad25)") (class "Default")
      (node (ref "BBBLACK") (pin "25") (pinfunction "GPIO1_0_25") (pintype "passive"))
    )
    (net (code "56") (name "unconnected-(BBBLACK-GPIO1_1-Pad24)") (class "Default")
      (node (ref "BBBLACK") (pin "24") (pinfunction "GPIO1_1_24") (pintype "passive"))
    )
    (net (code "57") (name "unconnected-(BBBLACK-GPIO1_2-Pad5)") (class "Default")
      (node (ref "BBBLACK") (pin "5") (pinfunction "GPIO1_2_5") (pintype "passive"))
    )
    (net (code "58") (name "unconnected-(BBBLACK-GPIO1_3-Pad6)") (class "Default")
      (node (ref "BBBLACK") (pin "6") (pinfunction "GPIO1_3_6") (pintype "passive"))
    )
    (net (code "59") (name "unconnected-(BBBLACK-GPIO1_4-Pad23)") (class "Default")
      (node (ref "BBBLACK") (pin "23") (pinfunction "GPIO1_4_23") (pintype "passive"))
    )
    (net (code "60") (name "unconnected-(BBBLACK-GPIO1_5-Pad22)") (class "Default")
      (node (ref "BBBLACK") (pin "22") (pinfunction "GPIO1_5_22") (pintype "passive"))
    )
    (net (code "61") (name "unconnected-(BBBLACK-GPIO1_6-Pad3)") (class "Default")
      (node (ref "BBBLACK") (pin "3") (pinfunction "GPIO1_6_3") (pintype "passive"))
    )
    (net (code "62") (name "unconnected-(BBBLACK-GPIO1_7-Pad4)") (class "Default")
      (node (ref "BBBLACK") (pin "4") (pinfunction "GPIO1_7_4") (pintype "passive"))
    )
    (net (code "63") (name "unconnected-(BBBLACK-GPIO1_14-Pad16)") (class "Default")
      (node (ref "BBBLACK") (pin "16") (pinfunction "GPIO1_14_16") (pintype "passive"))
    )
    (net (code "64") (name "unconnected-(BBBLACK-GPIO1_16-Pad61)") (class "Default")
      (node (ref "BBBLACK") (pin "61") (pinfunction "GPIO1_16_61") (pintype "passive"))
    )
    (net (code "65") (name "unconnected-(BBBLACK-GPIO1_30-Pad21)") (class "Default")
      (node (ref "BBBLACK") (pin "21") (pinfunction "GPIO1_30_21") (pintype "passive"))
    )
    (net (code "66") (name "unconnected-(BBBLACK-GPIO1_31-Pad20)") (class "Default")
      (node (ref "BBBLACK") (pin "20") (pinfunction "GPIO1_31_20") (pintype "passive"))
    )
    (net (code "67") (name "unconnected-(BBBLACK-GPIO2_6-Pad45)") (class "Default")
      (node (ref "BBBLACK") (pin "45") (pinfunction "GPIO2_6_45") (pintype "passive"))
    )
    (net (code "68") (name "unconnected-(BBBLACK-GPIO2_7-Pad46)") (class "Default")
      (node (ref "BBBLACK") (pin "46") (pinfunction "GPIO2_7_46") (pintype "passive"))
    )
    (net (code "69") (name "unconnected-(BBBLACK-GPIO2_8-Pad43)") (class "Default")
      (node (ref "BBBLACK") (pin "43") (pinfunction "GPIO2_8_43") (pintype "passive"))
    )
    (net (code "70") (name "unconnected-(BBBLACK-GPIO2_9-Pad44)") (class "Default")
      (node (ref "BBBLACK") (pin "44") (pinfunction "GPIO2_9_44") (pintype "passive"))
    )
    (net (code "71") (name "unconnected-(BBBLACK-GPIO2_10-Pad41)") (class "Default")
      (node (ref "BBBLACK") (pin "41") (pinfunction "GPIO2_10_41") (pintype "passive"))
    )
    (net (code "72") (name "unconnected-(BBBLACK-GPIO2_11-Pad42)") (class "Default")
      (node (ref "BBBLACK") (pin "42") (pinfunction "GPIO2_11_42") (pintype "passive"))
    )
    (net (code "73") (name "unconnected-(BBBLACK-GPIO2_12-Pad39)") (class "Default")
      (node (ref "BBBLACK") (pin "39") (pinfunction "GPIO2_12_39") (pintype "passive"))
    )
    (net (code "74") (name "unconnected-(BBBLACK-GPIO2_13-Pad40)") (class "Default")
      (node (ref "BBBLACK") (pin "40") (pinfunction "GPIO2_13_40") (pintype "passive"))
    )
    (net (code "75") (name "unconnected-(BBBLACK-GPIO2_22-Pad27)") (class "Default")
      (node (ref "BBBLACK") (pin "27") (pinfunction "GPIO2_22_27") (pintype "passive"))
    )
    (net (code "76") (name "unconnected-(BBBLACK-GPIO2_23-Pad29)") (class "Default")
      (node (ref "BBBLACK") (pin "29") (pinfunction "GPIO2_23_29") (pintype "passive"))
    )
    (net (code "77") (name "unconnected-(BBBLACK-GPIO2_24-Pad28)") (class "Default")
      (node (ref "BBBLACK") (pin "28") (pinfunction "GPIO2_24_28") (pintype "passive"))
    )
    (net (code "78") (name "unconnected-(BBBLACK-GPIO2_25-Pad30)") (class "Default")
      (node (ref "BBBLACK") (pin "30") (pinfunction "GPIO2_25_30") (pintype "passive"))
    )
    (net (code "79") (name "unconnected-(BBBLACK-GPIO3_19-Pad73)") (class "Default")
      (node (ref "BBBLACK") (pin "73") (pinfunction "GPIO3_19_73") (pintype "passive"))
    )
    (net (code "80") (name "unconnected-(BBBLACK-I2C1_SCL-Pad63)") (class "Default")
      (node (ref "BBBLACK") (pin "63") (pinfunction "I2C1_SCL_63") (pintype "passive"))
    )
    (net (code "81") (name "unconnected-(BBBLACK-I2C1_SDA-Pad64)") (class "Default")
      (node (ref "BBBLACK") (pin "64") (pinfunction "I2C1_SDA_64") (pintype "passive"))
    )
    (net (code "82") (name "unconnected-(BBBLACK-I2C2_SCL-Pad65)") (class "Default")
      (node (ref "BBBLACK") (pin "65") (pinfunction "I2C2_SCL_65") (pintype "passive"))
    )
    (net (code "83") (name "unconnected-(BBBLACK-I2C2_SDA-Pad66)") (class "Default")
      (node (ref "BBBLACK") (pin "66") (pinfunction "I2C2_SDA_66") (pintype "passive"))
    )
    (net (code "84") (name "unconnected-(BBBLACK-SPI1_CS0-Pad74)") (class "Default")
      (node (ref "BBBLACK") (pin "74") (pinfunction "SPI1_CS0_74") (pintype "passive"))
    )
    (net (code "85") (name "unconnected-(BBBLACK-SPI1_DI-Pad76)") (class "Default")
      (node (ref "BBBLACK") (pin "76") (pinfunction "SPI1_DI_76") (pintype "passive"))
    )
    (net (code "86") (name "unconnected-(BBBLACK-SPI1_DO-Pad75)") (class "Default")
      (node (ref "BBBLACK") (pin "75") (pinfunction "SPI1_DO_75") (pintype "passive"))
    )
    (net (code "87") (name "unconnected-(BBBLACK-SPI1_SCLK-Pad77)") (class "Default")
      (node (ref "BBBLACK") (pin "77") (pinfunction "SPI1_SCLK_77") (pintype "passive"))
    )
    (net (code "88") (name "unconnected-(BBBLACK-UART1_RXD-Pad72)") (class "Default")
      (node (ref "BBBLACK") (pin "72") (pinfunction "UART1_RXD_72") (pintype "passive"))
    )
    (net (code "89") (name "unconnected-(BBBLACK-UART1_TXD-Pad70)") (class "Default")
      (node (ref "BBBLACK") (pin "70") (pinfunction "UART1_TXD_70") (pintype "passive"))
    )
    (net (code "90") (name "unconnected-(BBBLACK-UART2_RXD-Pad68)") (class "Default")
      (node (ref "BBBLACK") (pin "68") (pinfunction "UART2_RXD_68") (pintype "passive"))
    )
    (net (code "91") (name "unconnected-(BBBLACK-UART2_TXD-Pad67)") (class "Default")
      (node (ref "BBBLACK") (pin "67") (pinfunction "UART2_TXD_67") (pintype "passive"))
    )
    (net (code "92") (name "unconnected-(BBBLACK-UART3_CTSN-Pad36)") (class "Default")
      (node (ref "BBBLACK") (pin "36") (pinfunction "UART3_CTSN_36") (pintype "passive"))
    )
    (net (code "93") (name "unconnected-(BBBLACK-UART3_RTSN-Pad34)") (class "Default")
      (node (ref "BBBLACK") (pin "34") (pinfunction "UART3_RTSN_34") (pintype "passive"))
    )
    (net (code "94") (name "unconnected-(BBBLACK-UART4_CTSN-Pad35)") (class "Default")
      (node (ref "BBBLACK") (pin "35") (pinfunction "UART4_CTSN_35") (pintype "passive"))
    )
    (net (code "95") (name "unconnected-(BBBLACK-UART4_RTSN-Pad33)") (class "Default")
      (node (ref "BBBLACK") (pin "33") (pinfunction "UART4_RTSN_33") (pintype "passive"))
    )
    (net (code "96") (name "unconnected-(BBBLACK-UART5_CTSN-Pad31)") (class "Default")
      (node (ref "BBBLACK") (pin "31") (pinfunction "UART5_CTSN_31") (pintype "passive"))
    )
    (net (code "97") (name "unconnected-(BBBLACK-UART5_RTSN-Pad32)") (class "Default")
      (node (ref "BBBLACK") (pin "32") (pinfunction "UART5_RTSN_32") (pintype "passive"))
    )
    (net (code "98") (name "unconnected-(BBBLACK-UART5_RXD-Pad38)") (class "Default")
      (node (ref "BBBLACK") (pin "38") (pinfunction "UART5_RXD_38") (pintype "passive"))
    )
    (net (code "99") (name "unconnected-(BBBLACK-UART5_TXD-Pad37)") (class "Default")
      (node (ref "BBBLACK") (pin "37") (pinfunction "UART5_TXD_37") (pintype "passive"))
    )
    (net (code "100") (name "unconnected-(BBBLACK-VDD_ADC-Pad78)") (class "Default")
      (node (ref "BBBLACK") (pin "78") (pinfunction "VDD_ADC_78") (pintype "passive"))
    )
  )
)
